# OOBD-Cup_v6.net
KiCad netlist of a schematic drawn in EAGLE
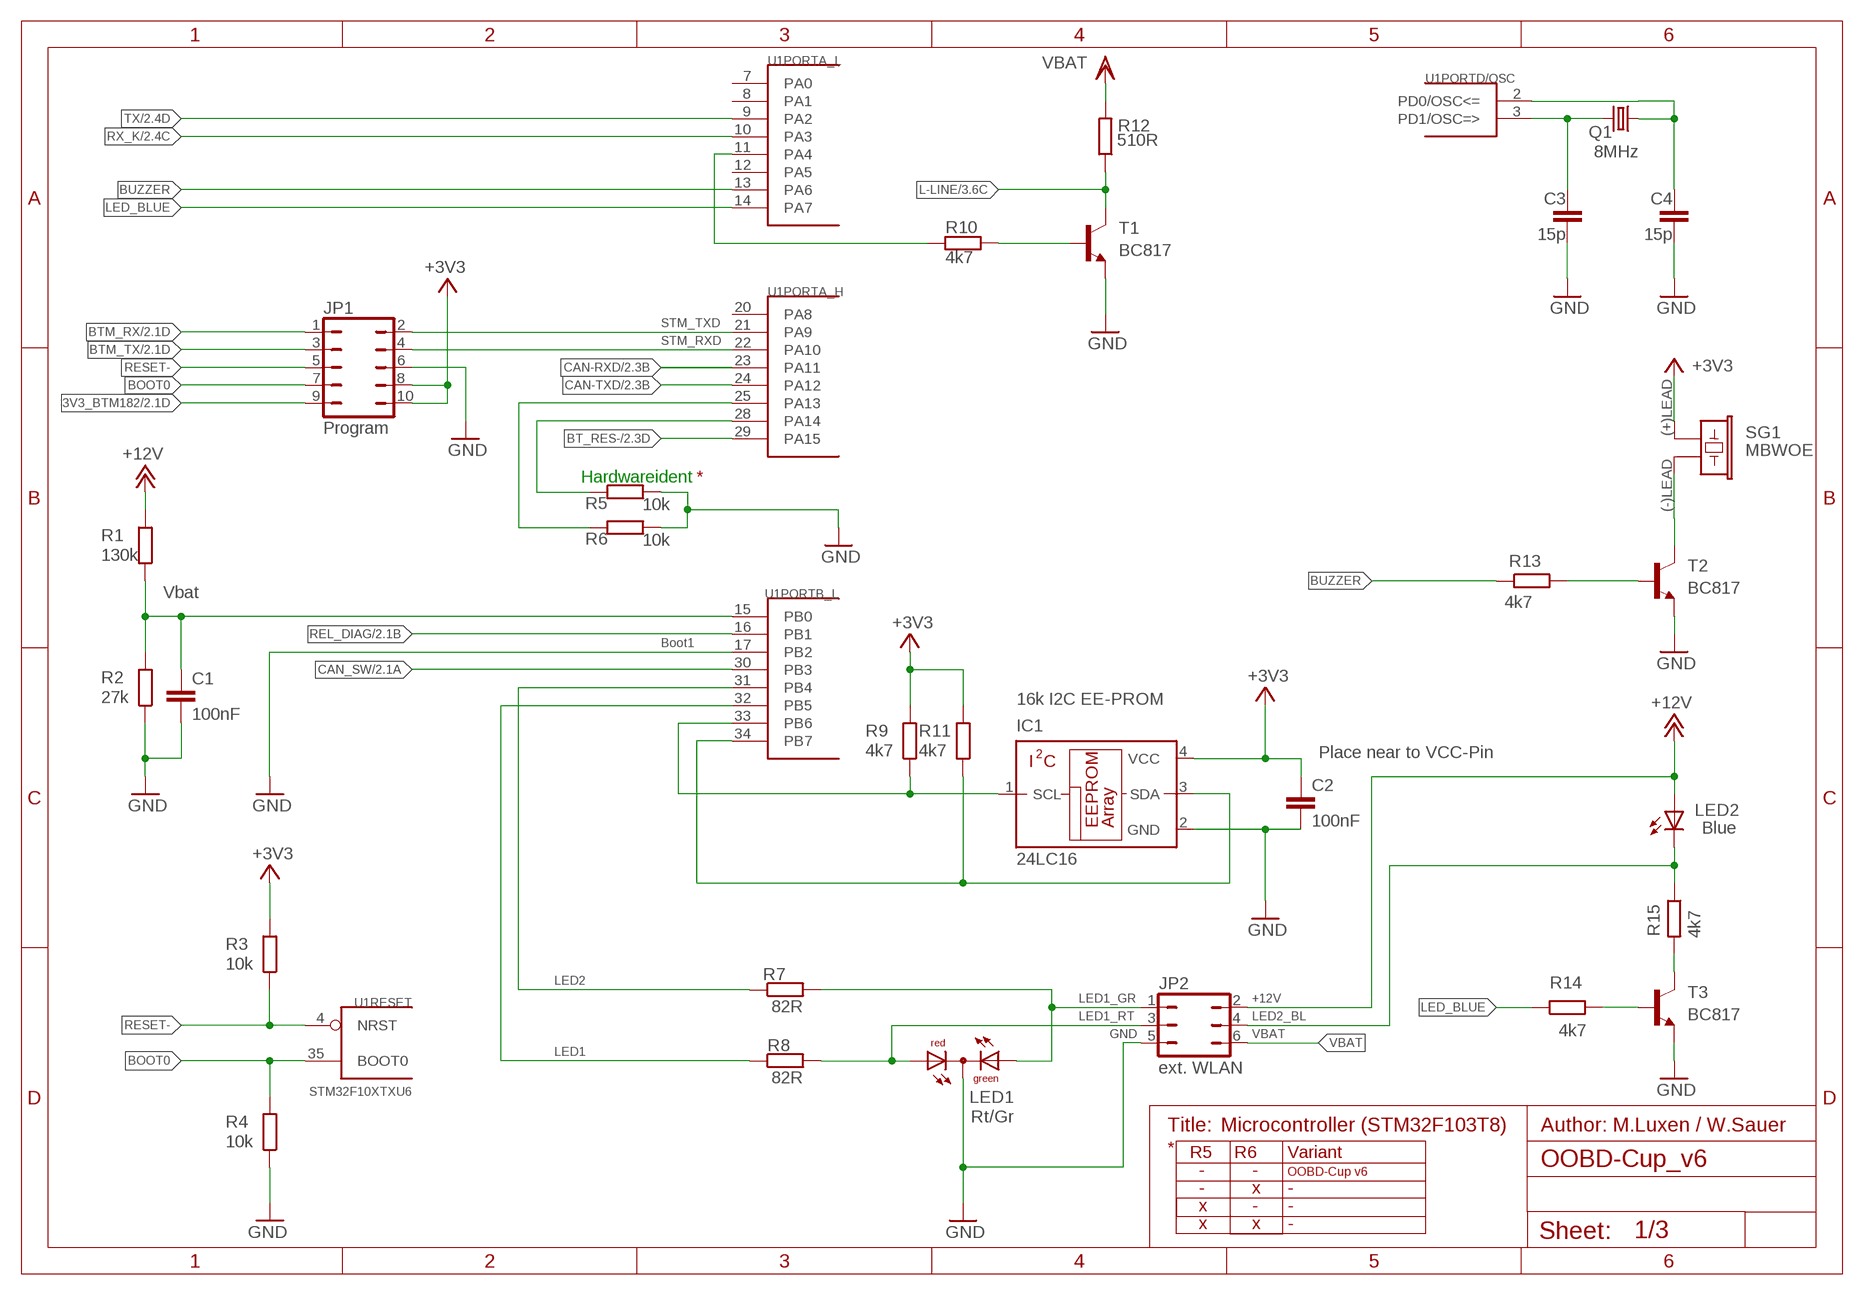
[diagram p0: schematic, sheet 1]
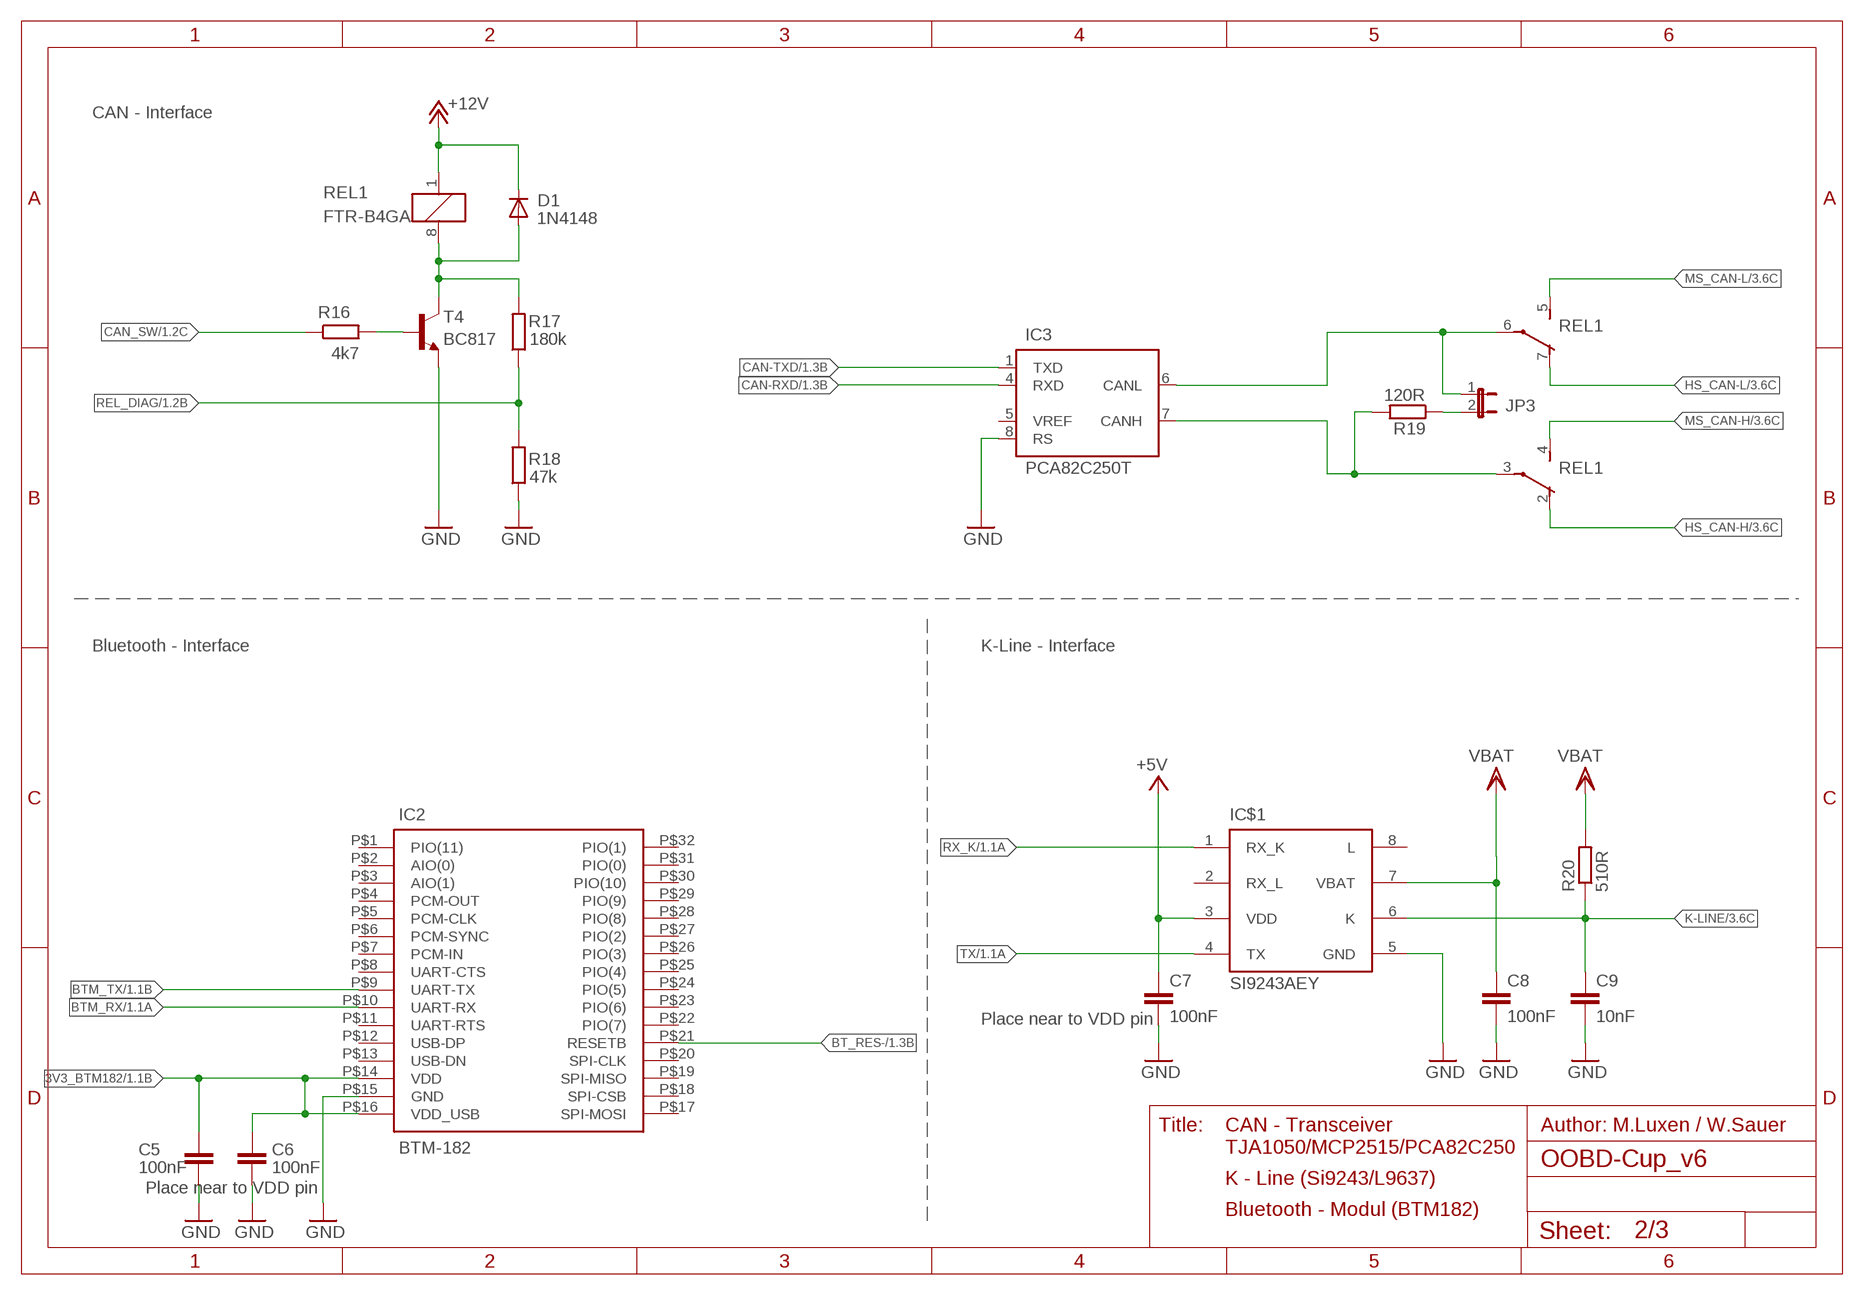
[diagram p1: schematic, sheet 2]
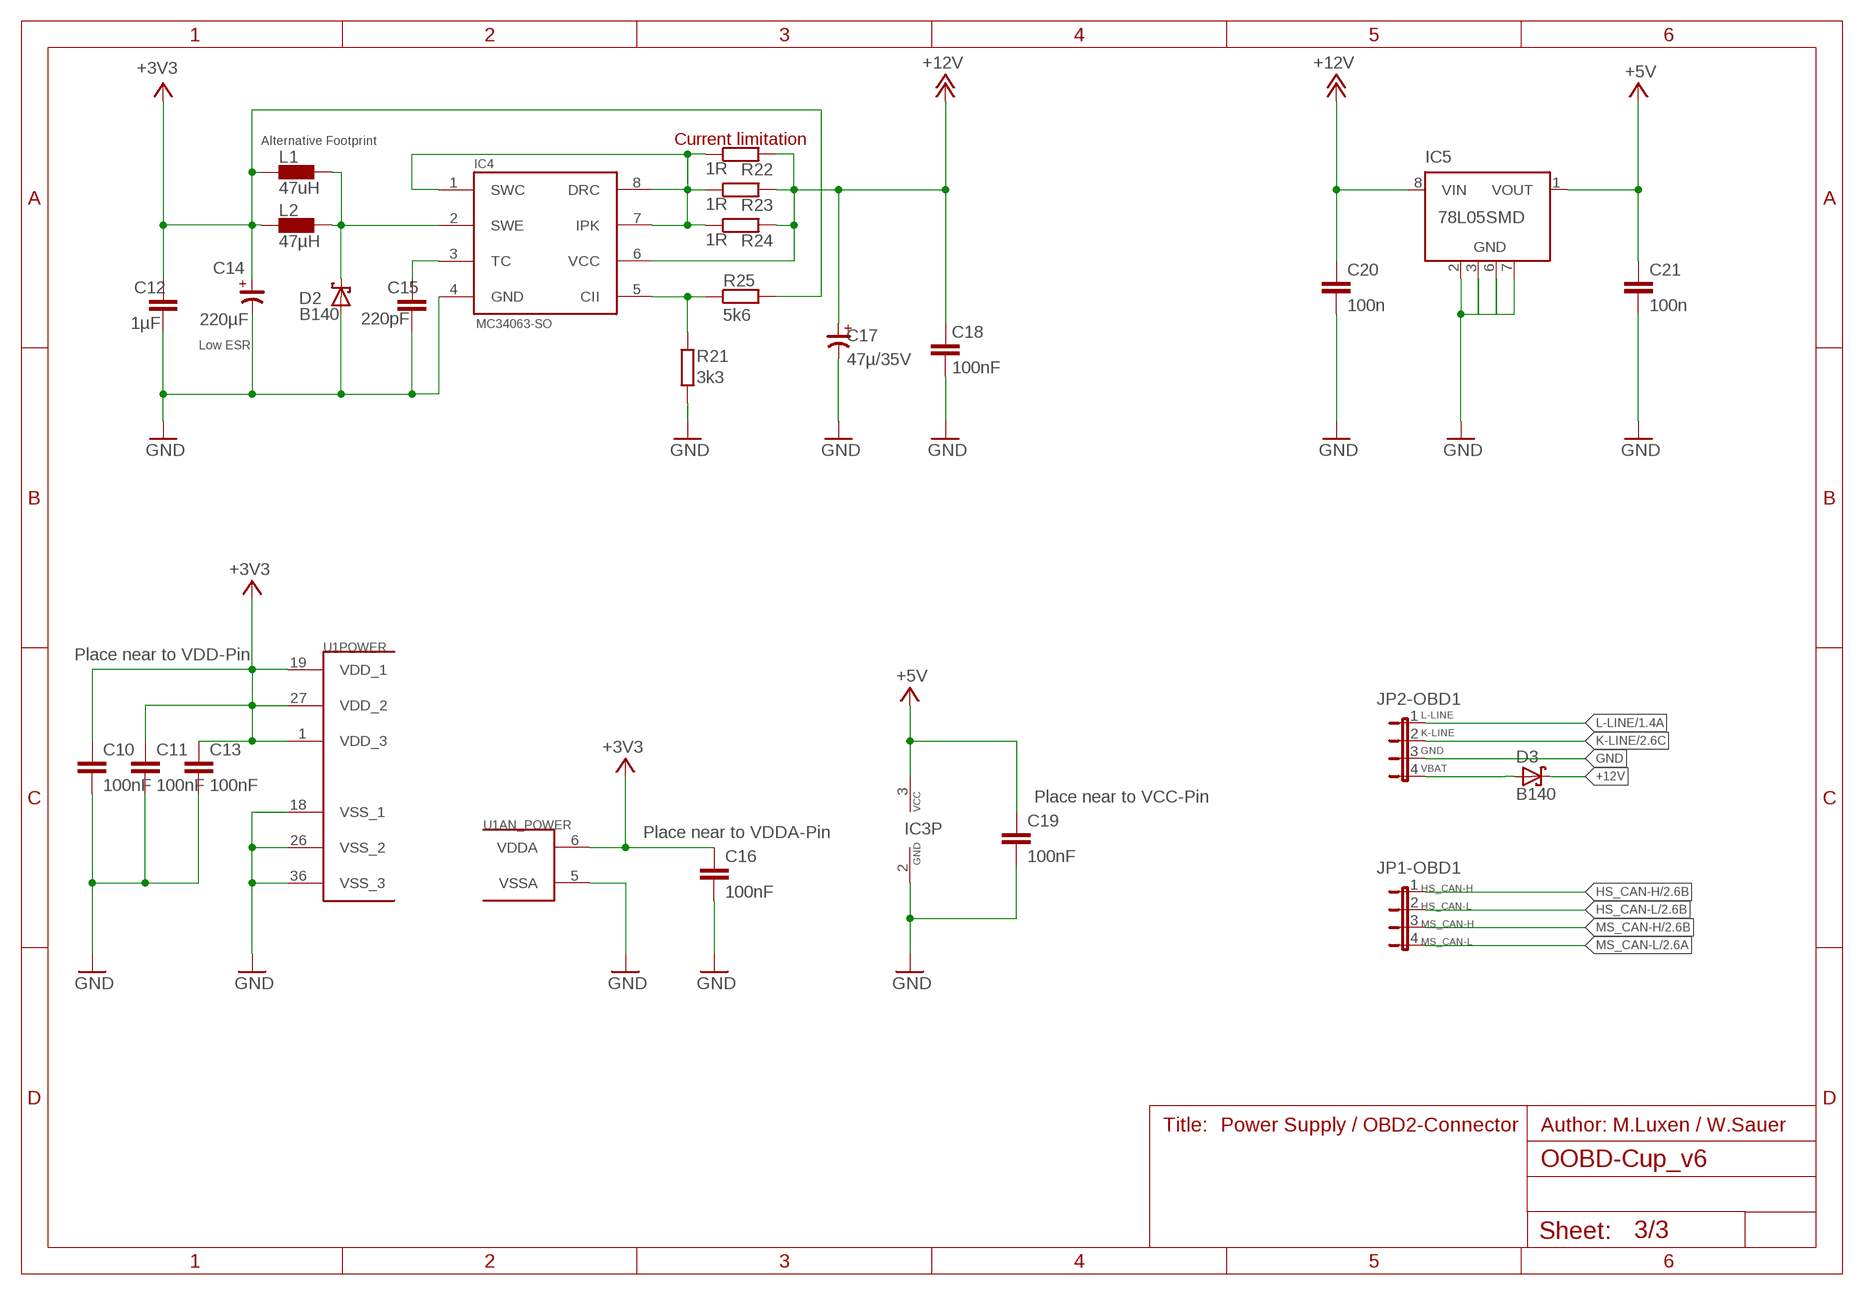
[diagram p2: schematic, sheet 3]

(export (version "E")
  (design (tool "Eeschema 10.0.6"))
  (components
    (comp (ref "C5")
      (value "100nF")
      (footprint "eagle-import:C0603")
      (libsource (lib "eagle-import") (part "C-EUC0603"))
    )
    (comp (ref "C6")
      (value "100nF")
      (footprint "eagle-import:C0603")
      (libsource (lib "eagle-import") (part "C-EUC0603"))
    )
    (comp (ref "C7")
      (value "100nF")
      (footprint "eagle-import:C0603")
      (libsource (lib "eagle-import") (part "resistor_C-EUC0603"))
    )
    (comp (ref "C8")
      (value "100nF")
      (footprint "eagle-import:C0603")
      (libsource (lib "eagle-import") (part "resistor_C-EUC0603"))
    )
    (comp (ref "C9")
      (value "10nF")
      (footprint "eagle-import:C0603")
      (libsource (lib "eagle-import") (part "resistor_C-EUC0603"))
    )
    (comp (ref "D1")
      (value "1N4148")
      (footprint "eagle-import:MINIMELF")
      (libsource (lib "eagle-import") (part "DIODE-MINIMELF"))
    )
    (comp (ref "IC$1")
      (value "SI9243AEY")
      (footprint "eagle-import:SO08")
      (libsource (lib "eagle-import") (part "SI9243AEY"))
    )
    (comp (ref "IC2")
      (value "BTM-182")
      (footprint "eagle-import:BTM-182")
      (libsource (lib "eagle-import") (part "BTM-182"))
    )
    (comp (ref "IC3")
      (value "PCA82C250T")
      (footprint "eagle-import:SO08")
      (libsource (lib "eagle-import") (part "PCA82C250T"))
    )
    (comp (ref "JP3")
      (value "JP1E")
      (footprint "eagle-import:JP1")
      (libsource (lib "eagle-import") (part "JP1E"))
    )
    (comp (ref "R16")
      (value "4k7")
      (footprint "eagle-import:R0603")
      (libsource (lib "eagle-import") (part "R-EU_R0603"))
    )
    (comp (ref "R17")
      (value "180k")
      (footprint "eagle-import:R0603")
      (libsource (lib "eagle-import") (part "R-EU_R0603"))
    )
    (comp (ref "R18")
      (value "47k")
      (footprint "eagle-import:R0603")
      (libsource (lib "eagle-import") (part "R-EU_R0603"))
    )
    (comp (ref "R19")
      (value "120R")
      (footprint "eagle-import:R0603")
      (libsource (lib "eagle-import") (part "resistor_R-EU_R0603"))
    )
    (comp (ref "R20")
      (value "510R")
      (footprint "eagle-import:R0603")
      (libsource (lib "eagle-import") (part "resistor_R-EU_R0603"))
    )
    (comp (ref "REL1")
      (value "FTR-B4GA")
      (footprint "eagle-import:FTR-B4GA")
      (fields (field (name "MPN") "FTR-B4GAxxxZ"))
      (libsource (lib "eagle-import") (part "FTR-B4GA"))
    )
    (comp (ref "T4")
      (value "BC817")
      (footprint "eagle-import:SOT23")
      (libsource (lib "eagle-import") (part "BC847"))
    )
    (comp (ref "C1")
      (value "100nF")
      (footprint "eagle-import:C0603")
      (libsource (lib "eagle-import") (part "resistor_C-EUC0603"))
    )
    (comp (ref "C2")
      (value "100nF")
      (footprint "eagle-import:C0603")
      (libsource (lib "eagle-import") (part "C-EUC0603"))
    )
    (comp (ref "C3")
      (value "15p")
      (footprint "eagle-import:C0603")
      (libsource (lib "eagle-import") (part "resistor_C-EUC0603"))
    )
    (comp (ref "C4")
      (value "15p")
      (footprint "eagle-import:C0603")
      (libsource (lib "eagle-import") (part "resistor_C-EUC0603"))
    )
    (comp (ref "IC1")
      (value "24LC16")
      (footprint "eagle-import:SOT23-5L")
      (fields (field (name "MF") "MICROCHIP") (field (name "MPN") "24LC00T-I/OT"))
      (libsource (lib "eagle-import") (part "2400OTLC"))
    )
    (comp (ref "JP1")
      (value "Program")
      (footprint "eagle-import:JP5Q")
      (libsource (lib "eagle-import") (part "JP5Q"))
    )
    (comp (ref "JP2")
      (value "ext. WLAN")
      (footprint "eagle-import:JP3Q")
      (libsource (lib "eagle-import") (part "JP3Q"))
    )
    (comp (ref "LED1")
      (value "Rt/Gr")
      (footprint "eagle-import:DUOLED2X5")
      (libsource (lib "eagle-import") (part "DUOLED2X5"))
    )
    (comp (ref "LED2")
      (value "Blue")
      (footprint "eagle-import:U57X32")
      (libsource (lib "eagle-import") (part "LEDSQR5.7X3.2"))
    )
    (comp (ref "Q1")
      (value "8MHz")
      (footprint "eagle-import:CTS406")
      (libsource (lib "eagle-import") (part "CRYSTALCTS406"))
    )
    (comp (ref "R1")
      (value "130k")
      (footprint "eagle-import:R0603")
      (libsource (lib "eagle-import") (part "resistor_R-EU_R0603"))
    )
    (comp (ref "R2")
      (value "27k")
      (footprint "eagle-import:R0603")
      (libsource (lib "eagle-import") (part "resistor_R-EU_R0603"))
    )
    (comp (ref "R3")
      (value "10k")
      (footprint "eagle-import:R0603")
      (libsource (lib "eagle-import") (part "resistor_R-EU_R0603"))
    )
    (comp (ref "R4")
      (value "10k")
      (footprint "eagle-import:R0603")
      (libsource (lib "eagle-import") (part "resistor_R-EU_R0603"))
    )
    (comp (ref "R5")
      (value "10k")
      (footprint "eagle-import:R0603")
      (libsource (lib "eagle-import") (part "R-EU_R0603"))
    )
    (comp (ref "R6")
      (value "10k")
      (footprint "eagle-import:R0603")
      (libsource (lib "eagle-import") (part "R-EU_R0603"))
    )
    (comp (ref "R7")
      (value "82R")
      (footprint "eagle-import:R0603")
      (libsource (lib "eagle-import") (part "R-EU_R0603"))
    )
    (comp (ref "R8")
      (value "82R")
      (footprint "eagle-import:R0603")
      (libsource (lib "eagle-import") (part "R-EU_R0603"))
    )
    (comp (ref "R9")
      (value "4k7")
      (footprint "eagle-import:R0603")
      (libsource (lib "eagle-import") (part "resistor_R-EU_R0603"))
    )
    (comp (ref "R10")
      (value "4k7")
      (footprint "eagle-import:R0603")
      (libsource (lib "eagle-import") (part "R-EU_R0603"))
    )
    (comp (ref "R11")
      (value "4k7")
      (footprint "eagle-import:R0603")
      (libsource (lib "eagle-import") (part "resistor_R-EU_R0603"))
    )
    (comp (ref "R12")
      (value "510R")
      (footprint "eagle-import:R0603")
      (libsource (lib "eagle-import") (part "R-EU_R0603"))
    )
    (comp (ref "R13")
      (value "4k7")
      (footprint "eagle-import:R0603")
      (libsource (lib "eagle-import") (part "R-EU_R0603"))
    )
    (comp (ref "R14")
      (value "4k7")
      (footprint "eagle-import:R0603")
      (libsource (lib "eagle-import") (part "R-EU_R0603"))
    )
    (comp (ref "R15")
      (value "4k7")
      (footprint "eagle-import:R0603")
      (libsource (lib "eagle-import") (part "R-EU_R0603"))
    )
    (comp (ref "SG1")
      (value "MBWOE")
      (footprint "eagle-import:BME0603SA")
      (fields (field (name "MF") "Grewus"))
      (libsource (lib "eagle-import") (part "MBWOE"))
    )
    (comp (ref "T1")
      (value "BC817")
      (footprint "eagle-import:SOT23")
      (libsource (lib "eagle-import") (part "BC847"))
    )
    (comp (ref "T2")
      (value "BC817")
      (footprint "eagle-import:SOT23")
      (libsource (lib "eagle-import") (part "BC847"))
    )
    (comp (ref "T3")
      (value "BC817")
      (footprint "eagle-import:SOT23")
      (libsource (lib "eagle-import") (part "BC847"))
    )
    (comp (ref "U1")
      (value "STM32F10XTXU6")
      (footprint "eagle-import:VFQFPN36")
      (libsource (lib "eagle-import") (part "STM32F10XTXU6"))
    )
    (comp (ref "C10")
      (value "100nF")
      (footprint "eagle-import:C0603")
      (libsource (lib "eagle-import") (part "resistor_C-EUC0603"))
    )
    (comp (ref "C11")
      (value "100nF")
      (footprint "eagle-import:C0603")
      (libsource (lib "eagle-import") (part "resistor_C-EUC0603"))
    )
    (comp (ref "C12")
      (value "1µF")
      (footprint "eagle-import:C0603K")
      (libsource (lib "eagle-import") (part "C-EUC0603K"))
    )
    (comp (ref "C13")
      (value "100nF")
      (footprint "eagle-import:C0603")
      (libsource (lib "eagle-import") (part "resistor_C-EUC0603"))
    )
    (comp (ref "C14")
      (value "220µF")
      (footprint "eagle-import:C6032-TE-C")
      (libsource (lib "eagle-import") (part "CP_6032-TE-C"))
    )
    (comp (ref "C15")
      (value "220pF")
      (footprint "eagle-import:C0603K")
      (libsource (lib "eagle-import") (part "C-EUC0603K"))
    )
    (comp (ref "C16")
      (value "100nF")
      (footprint "eagle-import:C0603")
      (libsource (lib "eagle-import") (part "resistor_C-EUC0603"))
    )
    (comp (ref "C17")
      (value "47µ/35V")
      (footprint "eagle-import:SV-D")
      (libsource (lib "eagle-import") (part "CP-SV-D"))
    )
    (comp (ref "C18")
      (value "100nF")
      (footprint "eagle-import:C0603K")
      (libsource (lib "eagle-import") (part "C-EUC0603K"))
    )
    (comp (ref "C19")
      (value "100nF")
      (footprint "eagle-import:C0603")
      (libsource (lib "eagle-import") (part "resistor_C-EUC0603"))
    )
    (comp (ref "C20")
      (value "100n")
      (footprint "eagle-import:C0603")
      (libsource (lib "eagle-import") (part "resistor_C-EUC0603"))
    )
    (comp (ref "C21")
      (value "100n")
      (footprint "eagle-import:C0603")
      (libsource (lib "eagle-import") (part "resistor_C-EUC0603"))
    )
    (comp (ref "D2")
      (value "B140")
      (footprint "eagle-import:SMB")
      (libsource (lib "eagle-import") (part "SCHOTTKY-DIODESMD"))
    )
    (comp (ref "D3")
      (value "B140")
      (footprint "eagle-import:SMB")
      (libsource (lib "eagle-import") (part "SCHOTTKY-DIODESMD"))
    )
    (comp (ref "IC4")
      (value "MC34063-SO")
      (footprint "eagle-import:SO8")
      (libsource (lib "eagle-import") (part "MC34063-SO"))
    )
    (comp (ref "IC5")
      (value "78L05SMD")
      (footprint "eagle-import:SO08")
      (libsource (lib "eagle-import") (part "78LSMD05"))
    )
    (comp (ref "JP1-OBD1")
      (value "JP4E")
      (footprint "eagle-import:JP4")
      (libsource (lib "eagle-import") (part "JP4E"))
    )
    (comp (ref "JP2-OBD1")
      (value "JP4E")
      (footprint "eagle-import:JP4")
      (libsource (lib "eagle-import") (part "JP4E"))
    )
    (comp (ref "L1")
      (value "47uH")
      (footprint "eagle-import:PIS2408")
      (libsource (lib "eagle-import") (part "PIS2408"))
    )
    (comp (ref "L2")
      (value "47µH")
      (footprint "eagle-import:07HCP-XXXX-50")
      (libsource (lib "eagle-import") (part "07HCP-XXXX-50"))
    )
    (comp (ref "R21")
      (value "3k3")
      (footprint "eagle-import:R0603")
      (libsource (lib "eagle-import") (part "R-EU_R0603"))
    )
    (comp (ref "R22")
      (value "1R")
      (footprint "eagle-import:R0805")
      (libsource (lib "eagle-import") (part "R-EU_R0805"))
    )
    (comp (ref "R23")
      (value "1R")
      (footprint "eagle-import:R0805")
      (libsource (lib "eagle-import") (part "R-EU_R0805"))
    )
    (comp (ref "R24")
      (value "1R")
      (footprint "eagle-import:R0805")
      (libsource (lib "eagle-import") (part "R-EU_R0805"))
    )
    (comp (ref "R25")
      (value "5k6")
      (footprint "eagle-import:R0603")
      (libsource (lib "eagle-import") (part "R-EU_R0603"))
    )
  )
  (nets
    (net (code "1") (name "+3V3") (class "Default")
      (node (ref "C10") (pin "1") (pinfunction "1_1") (pintype "passive"))
      (node (ref "C11") (pin "1") (pinfunction "1_1") (pintype "passive"))
      (node (ref "C12") (pin "1") (pinfunction "1_1") (pintype "passive"))
      (node (ref "C13") (pin "1") (pinfunction "1_1") (pintype "passive"))
      (node (ref "C14") (pin "+") (pinfunction "+_+") (pintype "passive"))
      (node (ref "C16") (pin "1") (pinfunction "1_1") (pintype "passive"))
      (node (ref "C2") (pin "1") (pinfunction "1_1") (pintype "passive"))
      (node (ref "IC1") (pin "4") (pinfunction "VCC_4") (pintype "power_in"))
      (node (ref "JP1") (pin "10") (pinfunction "10_10") (pintype "passive"))
      (node (ref "JP1") (pin "8") (pinfunction "8_8") (pintype "passive"))
      (node (ref "L1") (pin "P$1") (pinfunction "P$1_P$1") (pintype "bidirectional"))
      (node (ref "L2") (pin "1") (pinfunction "P$1_1") (pintype "bidirectional"))
      (node (ref "R11") (pin "2") (pinfunction "2_2") (pintype "passive"))
      (node (ref "R25") (pin "2") (pinfunction "2_2") (pintype "passive"))
      (node (ref "R3") (pin "2") (pinfunction "2_2") (pintype "passive"))
      (node (ref "R9") (pin "2") (pinfunction "2_2") (pintype "passive"))
      (node (ref "SG1") (pin "(+)LEAD") (pinfunction "1_(+)LEAD") (pintype "passive"))
      (node (ref "U1") (pin "1") (pinfunction "VDD_3_1") (pintype "power_in"))
      (node (ref "U1") (pin "19") (pinfunction "VDD_1_19") (pintype "power_in"))
      (node (ref "U1") (pin "27") (pinfunction "VDD_2_27") (pintype "power_in"))
      (node (ref "U1") (pin "6") (pinfunction "VDDA_6") (pintype "power_in"))
    )
    (net (code "2") (name "+5V") (class "Default")
      (node (ref "C19") (pin "1") (pinfunction "1_1") (pintype "passive"))
      (node (ref "C21") (pin "1") (pinfunction "1_1") (pintype "passive"))
      (node (ref "C7") (pin "1") (pinfunction "1_1") (pintype "passive"))
      (node (ref "IC$1") (pin "3") (pinfunction "VDD_3") (pintype "bidirectional"))
      (node (ref "IC3") (pin "3") (pinfunction "VCC_3") (pintype "power_in"))
      (node (ref "IC5") (pin "1") (pinfunction "VOUT_1") (pintype "output"))
    )
    (net (code "3") (name "+12V") (class "Default")
      (node (ref "C17") (pin "+") (pinfunction "+_+") (pintype "passive"))
      (node (ref "C18") (pin "1") (pinfunction "1_1") (pintype "passive"))
      (node (ref "C20") (pin "1") (pinfunction "1_1") (pintype "passive"))
      (node (ref "D1") (pin "C") (pinfunction "C_C") (pintype "passive"))
      (node (ref "D3") (pin "C") (pinfunction "C_C") (pintype "passive"))
      (node (ref "IC4") (pin "6") (pinfunction "VCC_6") (pintype "bidirectional"))
      (node (ref "IC5") (pin "8") (pinfunction "VIN_8") (pintype "passive"))
      (node (ref "JP2") (pin "2") (pinfunction "2_2") (pintype "passive"))
      (node (ref "LED2") (pin "A") (pinfunction "A_A") (pintype "passive"))
      (node (ref "R1") (pin "2") (pinfunction "2_2") (pintype "passive"))
      (node (ref "R22") (pin "2") (pinfunction "2_2") (pintype "passive"))
      (node (ref "R23") (pin "2") (pinfunction "2_2") (pintype "passive"))
      (node (ref "R24") (pin "2") (pinfunction "2_2") (pintype "passive"))
      (node (ref "REL1") (pin "1") (pinfunction "1_1") (pintype "passive"))
    )
    (net (code "4") (name "3V3_BTM182") (class "Default")
      (node (ref "C5") (pin "1") (pinfunction "1_1") (pintype "passive"))
      (node (ref "C6") (pin "1") (pinfunction "1_1") (pintype "passive"))
      (node (ref "IC2") (pin "P$14") (pinfunction "VDD_P$14") (pintype "power_in"))
      (node (ref "IC2") (pin "P$16") (pinfunction "VDD_USB_P$16") (pintype "power_in"))
      (node (ref "JP1") (pin "9") (pinfunction "9_9") (pintype "passive"))
    )
    (net (code "5") (name "BOOT0") (class "Default")
      (node (ref "JP1") (pin "7") (pinfunction "7_7") (pintype "passive"))
      (node (ref "R4") (pin "2") (pinfunction "2_2") (pintype "passive"))
      (node (ref "U1") (pin "35") (pinfunction "BOOT0_35") (pintype "input"))
    )
    (net (code "6") (name "BTM_RX") (class "Default")
      (node (ref "IC2") (pin "P$10") (pinfunction "UART-RX_P$10") (pintype "input"))
      (node (ref "JP1") (pin "1") (pinfunction "1_1") (pintype "passive"))
    )
    (net (code "7") (name "BTM_TX") (class "Default")
      (node (ref "IC2") (pin "P$9") (pinfunction "UART-TX_P$9") (pintype "output"))
      (node (ref "JP1") (pin "3") (pinfunction "3_3") (pintype "passive"))
    )
    (net (code "8") (name "BT_RES-") (class "Default")
      (node (ref "IC2") (pin "P$21") (pinfunction "RESETB_P$21") (pintype "input"))
      (node (ref "U1") (pin "29") (pinfunction "PA15_29") (pintype "bidirectional"))
    )
    (net (code "9") (name "BUZZER") (class "Default")
      (node (ref "R13") (pin "1") (pinfunction "1_1") (pintype "passive"))
      (node (ref "U1") (pin "13") (pinfunction "PA6_13") (pintype "bidirectional"))
    )
    (net (code "10") (name "CAN-RXD") (class "Default")
      (node (ref "IC3") (pin "4") (pinfunction "RXD_4") (pintype "bidirectional"))
      (node (ref "U1") (pin "23") (pinfunction "PA11_23") (pintype "bidirectional"))
    )
    (net (code "11") (name "CAN-TXD") (class "Default")
      (node (ref "IC3") (pin "1") (pinfunction "TXD_1") (pintype "bidirectional"))
      (node (ref "U1") (pin "24") (pinfunction "PA12_24") (pintype "bidirectional"))
    )
    (net (code "12") (name "CAN_SW") (class "Default")
      (node (ref "R16") (pin "1") (pinfunction "1_1") (pintype "passive"))
      (node (ref "U1") (pin "30") (pinfunction "PB3_30") (pintype "bidirectional"))
    )
    (net (code "13") (name "GND") (class "Default")
      (node (ref "C1") (pin "2") (pinfunction "2_2") (pintype "passive"))
      (node (ref "C10") (pin "2") (pinfunction "2_2") (pintype "passive"))
      (node (ref "C11") (pin "2") (pinfunction "2_2") (pintype "passive"))
      (node (ref "C12") (pin "2") (pinfunction "2_2") (pintype "passive"))
      (node (ref "C13") (pin "2") (pinfunction "2_2") (pintype "passive"))
      (node (ref "C14") (pin "-") (pinfunction "-_-") (pintype "passive"))
      (node (ref "C15") (pin "2") (pinfunction "2_2") (pintype "passive"))
      (node (ref "C16") (pin "2") (pinfunction "2_2") (pintype "passive"))
      (node (ref "C17") (pin "-") (pinfunction "-_-") (pintype "passive"))
      (node (ref "C18") (pin "2") (pinfunction "2_2") (pintype "passive"))
      (node (ref "C19") (pin "2") (pinfunction "2_2") (pintype "passive"))
      (node (ref "C2") (pin "2") (pinfunction "2_2") (pintype "passive"))
      (node (ref "C20") (pin "2") (pinfunction "2_2") (pintype "passive"))
      (node (ref "C21") (pin "2") (pinfunction "2_2") (pintype "passive"))
      (node (ref "C3") (pin "1") (pinfunction "1_1") (pintype "passive"))
      (node (ref "C4") (pin "1") (pinfunction "1_1") (pintype "passive"))
      (node (ref "C5") (pin "2") (pinfunction "2_2") (pintype "passive"))
      (node (ref "C6") (pin "2") (pinfunction "2_2") (pintype "passive"))
      (node (ref "C7") (pin "2") (pinfunction "2_2") (pintype "passive"))
      (node (ref "C8") (pin "2") (pinfunction "2_2") (pintype "passive"))
      (node (ref "C9") (pin "2") (pinfunction "2_2") (pintype "passive"))
      (node (ref "D2") (pin "A") (pinfunction "A_A") (pintype "passive"))
      (node (ref "IC$1") (pin "5") (pinfunction "GND_5") (pintype "bidirectional"))
      (node (ref "IC1") (pin "2") (pinfunction "GND_2") (pintype "power_in"))
      (node (ref "IC2") (pin "P$15") (pinfunction "GND_P$15") (pintype "power_in"))
      (node (ref "IC3") (pin "2") (pinfunction "GND_2") (pintype "power_in"))
      (node (ref "IC3") (pin "8") (pinfunction "RS_8") (pintype "bidirectional"))
      (node (ref "IC4") (pin "4") (pinfunction "GND_4") (pintype "power_in"))
      (node (ref "IC5") (pin "2") (pinfunction "GND_2") (pintype "power_in"))
      (node (ref "IC5") (pin "3") (pinfunction "GND_3") (pintype "power_in"))
      (node (ref "IC5") (pin "6") (pinfunction "GND_6") (pintype "power_in"))
      (node (ref "IC5") (pin "7") (pinfunction "GND_7") (pintype "power_in"))
      (node (ref "JP1") (pin "6") (pinfunction "6_6") (pintype "passive"))
      (node (ref "JP2") (pin "5") (pinfunction "5_5") (pintype "passive"))
      (node (ref "JP2-OBD1") (pin "3") (pinfunction "3_3") (pintype "passive"))
      (node (ref "LED1") (pin "K") (pinfunction "C_K") (pintype "passive"))
      (node (ref "R18") (pin "1") (pinfunction "1_1") (pintype "passive"))
      (node (ref "R2") (pin "1") (pinfunction "1_1") (pintype "passive"))
      (node (ref "R21") (pin "2") (pinfunction "2_2") (pintype "passive"))
      (node (ref "R4") (pin "1") (pinfunction "1_1") (pintype "passive"))
      (node (ref "R5") (pin "2") (pinfunction "2_2") (pintype "passive"))
      (node (ref "R6") (pin "2") (pinfunction "2_2") (pintype "passive"))
      (node (ref "T1") (pin "2") (pinfunction "E_2") (pintype "passive"))
      (node (ref "T2") (pin "2") (pinfunction "E_2") (pintype "passive"))
      (node (ref "T3") (pin "2") (pinfunction "E_2") (pintype "passive"))
      (node (ref "T4") (pin "2") (pinfunction "E_2") (pintype "passive"))
      (node (ref "U1") (pin "17") (pinfunction "PB2_17") (pintype "bidirectional"))
      (node (ref "U1") (pin "18") (pinfunction "VSS_1_18") (pintype "power_in"))
      (node (ref "U1") (pin "26") (pinfunction "VSS_2_26") (pintype "power_in"))
      (node (ref "U1") (pin "36") (pinfunction "VSS_3_36") (pintype "power_in"))
      (node (ref "U1") (pin "5") (pinfunction "VSSA_5") (pintype "power_in"))
    )
    (net (code "14") (name "HS_CAN-H") (class "Default")
      (node (ref "JP1-OBD1") (pin "1") (pinfunction "1_1") (pintype "passive"))
      (node (ref "REL1") (pin "2") (pinfunction "O_2") (pintype "passive"))
    )
    (net (code "15") (name "HS_CAN-L") (class "Default")
      (node (ref "JP1-OBD1") (pin "2") (pinfunction "2_2") (pintype "passive"))
      (node (ref "REL1") (pin "7") (pinfunction "O_7") (pintype "passive"))
    )
    (net (code "16") (name "K-LINE") (class "Default")
      (node (ref "C9") (pin "1") (pinfunction "1_1") (pintype "passive"))
      (node (ref "IC$1") (pin "6") (pinfunction "K_6") (pintype "bidirectional"))
      (node (ref "JP2-OBD1") (pin "2") (pinfunction "2_2") (pintype "passive"))
      (node (ref "R20") (pin "1") (pinfunction "1_1") (pintype "passive"))
    )
    (net (code "17") (name "L-LINE") (class "Default")
      (node (ref "JP2-OBD1") (pin "1") (pinfunction "1_1") (pintype "passive"))
      (node (ref "R12") (pin "1") (pinfunction "1_1") (pintype "passive"))
      (node (ref "T1") (pin "3") (pinfunction "C_3") (pintype "passive"))
    )
    (net (code "18") (name "LED1") (class "Default")
      (node (ref "R8") (pin "1") (pinfunction "1_1") (pintype "passive"))
      (node (ref "U1") (pin "32") (pinfunction "PB5_32") (pintype "bidirectional"))
    )
    (net (code "19") (name "LED1_GR") (class "Default")
      (node (ref "JP2") (pin "1") (pinfunction "1_1") (pintype "passive"))
      (node (ref "LED1") (pin "AG") (pinfunction "AG_AG") (pintype "passive"))
      (node (ref "R7") (pin "2") (pinfunction "2_2") (pintype "passive"))
    )
    (net (code "20") (name "LED1_RT") (class "Default")
      (node (ref "JP2") (pin "3") (pinfunction "3_3") (pintype "passive"))
      (node (ref "LED1") (pin "AR") (pinfunction "AR_AR") (pintype "passive"))
      (node (ref "R8") (pin "2") (pinfunction "2_2") (pintype "passive"))
    )
    (net (code "21") (name "LED2") (class "Default")
      (node (ref "R7") (pin "1") (pinfunction "1_1") (pintype "passive"))
      (node (ref "U1") (pin "31") (pinfunction "PB4_31") (pintype "bidirectional"))
    )
    (net (code "22") (name "LED2_BL") (class "Default")
      (node (ref "JP2") (pin "4") (pinfunction "4_4") (pintype "passive"))
      (node (ref "LED2") (pin "K") (pinfunction "C_K") (pintype "passive"))
      (node (ref "R15") (pin "1") (pinfunction "1_1") (pintype "passive"))
    )
    (net (code "23") (name "LED_BLUE") (class "Default")
      (node (ref "R14") (pin "1") (pinfunction "1_1") (pintype "passive"))
      (node (ref "U1") (pin "14") (pinfunction "PA7_14") (pintype "bidirectional"))
    )
    (net (code "24") (name "MS_CAN-H") (class "Default")
      (node (ref "JP1-OBD1") (pin "3") (pinfunction "3_3") (pintype "passive"))
      (node (ref "REL1") (pin "4") (pinfunction "S_4") (pintype "passive"))
    )
    (net (code "25") (name "MS_CAN-L") (class "Default")
      (node (ref "JP1-OBD1") (pin "4") (pinfunction "4_4") (pintype "passive"))
      (node (ref "REL1") (pin "5") (pinfunction "S_5") (pintype "passive"))
    )
    (net (code "26") (name "Net-(IC1-SCL)") (class "Default")
      (node (ref "IC1") (pin "1") (pinfunction "SCL_1") (pintype "input"))
      (node (ref "R9") (pin "1") (pinfunction "1_1") (pintype "passive"))
      (node (ref "U1") (pin "33") (pinfunction "PB6_33") (pintype "bidirectional"))
    )
    (net (code "27") (name "Net-(IC1-SDA)") (class "Default")
      (node (ref "IC1") (pin "3") (pinfunction "SDA_3") (pintype "bidirectional"))
      (node (ref "R11") (pin "1") (pinfunction "1_1") (pintype "passive"))
      (node (ref "U1") (pin "34") (pinfunction "PB7_34") (pintype "bidirectional"))
    )
    (net (code "28") (name "Net-(IC3A-CANH)") (class "Default")
      (node (ref "IC3") (pin "7") (pinfunction "CANH_7") (pintype "bidirectional"))
      (node (ref "R19") (pin "2") (pinfunction "2_2") (pintype "passive"))
      (node (ref "REL1") (pin "3") (pinfunction "P_3") (pintype "passive"))
    )
    (net (code "29") (name "Net-(IC3A-CANL)") (class "Default")
      (node (ref "IC3") (pin "6") (pinfunction "CANL_6") (pintype "bidirectional"))
      (node (ref "JP3") (pin "1") (pinfunction "1_1") (pintype "passive"))
      (node (ref "REL1") (pin "6") (pinfunction "P_6") (pintype "passive"))
    )
    (net (code "30") (name "Net-(IC4-CII)") (class "Default")
      (node (ref "IC4") (pin "5") (pinfunction "CII_5") (pintype "bidirectional"))
      (node (ref "R21") (pin "1") (pinfunction "1_1") (pintype "passive"))
      (node (ref "R25") (pin "1") (pinfunction "1_1") (pintype "passive"))
    )
    (net (code "31") (name "Net-(IC4-DRC)") (class "Default")
      (node (ref "IC4") (pin "1") (pinfunction "SWC_1") (pintype "bidirectional"))
      (node (ref "IC4") (pin "7") (pinfunction "IPK_7") (pintype "bidirectional"))
      (node (ref "IC4") (pin "8") (pinfunction "DRC_8") (pintype "bidirectional"))
      (node (ref "R22") (pin "1") (pinfunction "1_1") (pintype "passive"))
      (node (ref "R23") (pin "1") (pinfunction "1_1") (pintype "passive"))
      (node (ref "R24") (pin "1") (pinfunction "1_1") (pintype "passive"))
    )
    (net (code "32") (name "Net-(IC4-SWE)") (class "Default")
      (node (ref "D2") (pin "C") (pinfunction "C_C") (pintype "passive"))
      (node (ref "IC4") (pin "2") (pinfunction "SWE_2") (pintype "bidirectional"))
      (node (ref "L1") (pin "P$2") (pinfunction "P$2_P$2") (pintype "bidirectional"))
      (node (ref "L2") (pin "2") (pinfunction "P$2_2") (pintype "bidirectional"))
    )
    (net (code "33") (name "Net-(IC4-TC)") (class "Default")
      (node (ref "C15") (pin "1") (pinfunction "1_1") (pintype "passive"))
      (node (ref "IC4") (pin "3") (pinfunction "TC_3") (pintype "bidirectional"))
    )
    (net (code "34") (name "Net-(JP3-Pad2)") (class "Default")
      (node (ref "JP3") (pin "2") (pinfunction "2_2") (pintype "passive"))
      (node (ref "R19") (pin "1") (pinfunction "1_1") (pintype "passive"))
    )
    (net (code "35") (name "Net-(Q1-2)") (class "Default")
      (node (ref "C3") (pin "2") (pinfunction "2_2") (pintype "passive"))
      (node (ref "Q1") (pin "3") (pinfunction "2_3") (pintype "passive"))
      (node (ref "U1") (pin "3") (pinfunction "PD1/OSC=>_3") (pintype "bidirectional"))
    )
    (net (code "36") (name "Net-(REL1A-2)") (class "Default")
      (node (ref "D1") (pin "A") (pinfunction "A_A") (pintype "passive"))
      (node (ref "R17") (pin "2") (pinfunction "2_2") (pintype "passive"))
      (node (ref "REL1") (pin "8") (pinfunction "2_8") (pintype "passive"))
      (node (ref "T4") (pin "3") (pinfunction "C_3") (pintype "passive"))
    )
    (net (code "37") (name "Net-(SG1-2)") (class "Default")
      (node (ref "SG1") (pin "(-)LEAD") (pinfunction "2_(-)LEAD") (pintype "passive"))
      (node (ref "T2") (pin "3") (pinfunction "C_3") (pintype "passive"))
    )
    (net (code "38") (name "Net-(T1-B)") (class "Default")
      (node (ref "R10") (pin "2") (pinfunction "2_2") (pintype "passive"))
      (node (ref "T1") (pin "1") (pinfunction "B_1") (pintype "passive"))
    )
    (net (code "39") (name "Net-(T2-B)") (class "Default")
      (node (ref "R13") (pin "2") (pinfunction "2_2") (pintype "passive"))
      (node (ref "T2") (pin "1") (pinfunction "B_1") (pintype "passive"))
    )
    (net (code "40") (name "Net-(T3-B)") (class "Default")
      (node (ref "R14") (pin "2") (pinfunction "2_2") (pintype "passive"))
      (node (ref "T3") (pin "1") (pinfunction "B_1") (pintype "passive"))
    )
    (net (code "41") (name "Net-(T3-C)") (class "Default")
      (node (ref "R15") (pin "2") (pinfunction "2_2") (pintype "passive"))
      (node (ref "T3") (pin "3") (pinfunction "C_3") (pintype "passive"))
    )
    (net (code "42") (name "Net-(T4-B)") (class "Default")
      (node (ref "R16") (pin "2") (pinfunction "2_2") (pintype "passive"))
      (node (ref "T4") (pin "1") (pinfunction "B_1") (pintype "passive"))
    )
    (net (code "43") (name "Net-(U1B-PA13)") (class "Default")
      (node (ref "R6") (pin "1") (pinfunction "1_1") (pintype "passive"))
      (node (ref "U1") (pin "25") (pinfunction "PA13_25") (pintype "bidirectional"))
    )
    (net (code "44") (name "Net-(U1B-PA14)") (class "Default")
      (node (ref "R5") (pin "1") (pinfunction "1_1") (pintype "passive"))
      (node (ref "U1") (pin "28") (pinfunction "PA14_28") (pintype "bidirectional"))
    )
    (net (code "45") (name "Net-(U1C-PA4)") (class "Default")
      (node (ref "R10") (pin "1") (pinfunction "1_1") (pintype "passive"))
      (node (ref "U1") (pin "11") (pinfunction "PA4_11") (pintype "bidirectional"))
    )
    (net (code "46") (name "Net-(U1D-PB0)") (class "Default")
      (node (ref "C1") (pin "1") (pinfunction "1_1") (pintype "passive"))
      (node (ref "R1") (pin "1") (pinfunction "1_1") (pintype "passive"))
      (node (ref "R2") (pin "2") (pinfunction "2_2") (pintype "passive"))
      (node (ref "U1") (pin "15") (pinfunction "PB0_15") (pintype "bidirectional"))
    )
    (net (code "47") (name "Net-(U1E-PD0{slash}OSC<=)") (class "Default")
      (node (ref "C4") (pin "2") (pinfunction "2_2") (pintype "passive"))
      (node (ref "Q1") (pin "1") (pinfunction "1_1") (pintype "passive"))
      (node (ref "U1") (pin "2") (pinfunction "PD0/OSC<=_2") (pintype "bidirectional"))
    )
    (net (code "48") (name "REL_DIAG") (class "Default")
      (node (ref "R17") (pin "1") (pinfunction "1_1") (pintype "passive"))
      (node (ref "R18") (pin "2") (pinfunction "2_2") (pintype "passive"))
      (node (ref "U1") (pin "16") (pinfunction "PB1_16") (pintype "bidirectional"))
    )
    (net (code "49") (name "RESET-") (class "Default")
      (node (ref "JP1") (pin "5") (pinfunction "5_5") (pintype "passive"))
      (node (ref "R3") (pin "1") (pinfunction "1_1") (pintype "passive"))
      (node (ref "U1") (pin "4") (pinfunction "NRST_4") (pintype "input"))
    )
    (net (code "50") (name "RX_K") (class "Default")
      (node (ref "IC$1") (pin "1") (pinfunction "RX_K_1") (pintype "bidirectional"))
      (node (ref "U1") (pin "10") (pinfunction "PA3_10") (pintype "bidirectional"))
    )
    (net (code "51") (name "STM_RXD") (class "Default")
      (node (ref "JP1") (pin "4") (pinfunction "4_4") (pintype "passive"))
      (node (ref "U1") (pin "22") (pinfunction "PA10_22") (pintype "bidirectional"))
    )
    (net (code "52") (name "STM_TXD") (class "Default")
      (node (ref "JP1") (pin "2") (pinfunction "2_2") (pintype "passive"))
      (node (ref "U1") (pin "21") (pinfunction "PA9_21") (pintype "bidirectional"))
    )
    (net (code "53") (name "TX") (class "Default")
      (node (ref "IC$1") (pin "4") (pinfunction "TX_4") (pintype "bidirectional"))
      (node (ref "U1") (pin "9") (pinfunction "PA2_9") (pintype "bidirectional"))
    )
    (net (code "54") (name "VBAT") (class "Default")
      (node (ref "C8") (pin "1") (pinfunction "1_1") (pintype "passive"))
      (node (ref "D3") (pin "A") (pinfunction "A_A") (pintype "passive"))
      (node (ref "IC$1") (pin "7") (pinfunction "VBAT_7") (pintype "bidirectional"))
      (node (ref "JP2") (pin "6") (pinfunction "6_6") (pintype "passive"))
      (node (ref "JP2-OBD1") (pin "4") (pinfunction "4_4") (pintype "passive"))
      (node (ref "R12") (pin "2") (pinfunction "2_2") (pintype "passive"))
      (node (ref "R20") (pin "2") (pinfunction "2_2") (pintype "passive"))
    )
    (net (code "55") (name "unconnected-(IC$1-L-Pad8)") (class "Default")
      (node (ref "IC$1") (pin "8") (pinfunction "L_8") (pintype "bidirectional"))
    )
    (net (code "56") (name "unconnected-(IC$1-RX_L-Pad2)") (class "Default")
      (node (ref "IC$1") (pin "2") (pinfunction "RX_L_2") (pintype "bidirectional"))
    )
    (net (code "57") (name "unconnected-(IC2-AIO(0)-PadP$2)") (class "Default")
      (node (ref "IC2") (pin "P$2") (pinfunction "AIO(0)_P$2") (pintype "bidirectional"))
    )
    (net (code "58") (name "unconnected-(IC2-AIO(1)-PadP$3)") (class "Default")
      (node (ref "IC2") (pin "P$3") (pinfunction "AIO(1)_P$3") (pintype "bidirectional"))
    )
    (net (code "59") (name "unconnected-(IC2-PCM-CLK-PadP$5)") (class "Default")
      (node (ref "IC2") (pin "P$5") (pinfunction "PCM-CLK_P$5") (pintype "bidirectional"))
    )
    (net (code "60") (name "unconnected-(IC2-PCM-IN-PadP$7)") (class "Default")
      (node (ref "IC2") (pin "P$7") (pinfunction "PCM-IN_P$7") (pintype "input"))
    )
    (net (code "61") (name "unconnected-(IC2-PCM-OUT-PadP$4)") (class "Default")
      (node (ref "IC2") (pin "P$4") (pinfunction "PCM-OUT_P$4") (pintype "output"))
    )
    (net (code "62") (name "unconnected-(IC2-PCM-SYNC-PadP$6)") (class "Default")
      (node (ref "IC2") (pin "P$6") (pinfunction "PCM-SYNC_P$6") (pintype "bidirectional"))
    )
    (net (code "63") (name "unconnected-(IC2-PIO(0)-PadP$31)") (class "Default")
      (node (ref "IC2") (pin "P$31") (pinfunction "PIO(0)_P$31") (pintype "bidirectional"))
    )
    (net (code "64") (name "unconnected-(IC2-PIO(1)-PadP$32)") (class "Default")
      (node (ref "IC2") (pin "P$32") (pinfunction "PIO(1)_P$32") (pintype "bidirectional"))
    )
    (net (code "65") (name "unconnected-(IC2-PIO(2)-PadP$27)") (class "Default")
      (node (ref "IC2") (pin "P$27") (pinfunction "PIO(2)_P$27") (pintype "bidirectional"))
    )
    (net (code "66") (name "unconnected-(IC2-PIO(3)-PadP$26)") (class "Default")
      (node (ref "IC2") (pin "P$26") (pinfunction "PIO(3)_P$26") (pintype "bidirectional"))
    )
    (net (code "67") (name "unconnected-(IC2-PIO(4)-PadP$25)") (class "Default")
      (node (ref "IC2") (pin "P$25") (pinfunction "PIO(4)_P$25") (pintype "bidirectional"))
    )
    (net (code "68") (name "unconnected-(IC2-PIO(5)-PadP$24)") (class "Default")
      (node (ref "IC2") (pin "P$24") (pinfunction "PIO(5)_P$24") (pintype "bidirectional"))
    )
    (net (code "69") (name "unconnected-(IC2-PIO(6)-PadP$23)") (class "Default")
      (node (ref "IC2") (pin "P$23") (pinfunction "PIO(6)_P$23") (pintype "bidirectional"))
    )
    (net (code "70") (name "unconnected-(IC2-PIO(7)-PadP$22)") (class "Default")
      (node (ref "IC2") (pin "P$22") (pinfunction "PIO(7)_P$22") (pintype "bidirectional"))
    )
    (net (code "71") (name "unconnected-(IC2-PIO(8)-PadP$28)") (class "Default")
      (node (ref "IC2") (pin "P$28") (pinfunction "PIO(8)_P$28") (pintype "bidirectional"))
    )
    (net (code "72") (name "unconnected-(IC2-PIO(9)-PadP$29)") (class "Default")
      (node (ref "IC2") (pin "P$29") (pinfunction "PIO(9)_P$29") (pintype "bidirectional"))
    )
    (net (code "73") (name "unconnected-(IC2-PIO(10)-PadP$30)") (class "Default")
      (node (ref "IC2") (pin "P$30") (pinfunction "PIO(10)_P$30") (pintype "bidirectional"))
    )
    (net (code "74") (name "unconnected-(IC2-PIO(11)-PadP$1)") (class "Default")
      (node (ref "IC2") (pin "P$1") (pinfunction "PIO(11)_P$1") (pintype "bidirectional"))
    )
    (net (code "75") (name "unconnected-(IC2-SPI-CLK-PadP$20)") (class "Default")
      (node (ref "IC2") (pin "P$20") (pinfunction "SPI-CLK_P$20") (pintype "input"))
    )
    (net (code "76") (name "unconnected-(IC2-SPI-CSB-PadP$18)") (class "Default")
      (node (ref "IC2") (pin "P$18") (pinfunction "SPI-CSB_P$18") (pintype "input"))
    )
    (net (code "77") (name "unconnected-(IC2-SPI-MISO-PadP$19)") (class "Default")
      (node (ref "IC2") (pin "P$19") (pinfunction "SPI-MISO_P$19") (pintype "output"))
    )
    (net (code "78") (name "unconnected-(IC2-SPI-MOSI-PadP$17)") (class "Default")
      (node (ref "IC2") (pin "P$17") (pinfunction "SPI-MOSI_P$17") (pintype "input"))
    )
    (net (code "79") (name "unconnected-(IC2-UART-CTS-PadP$8)") (class "Default")
      (node (ref "IC2") (pin "P$8") (pinfunction "UART-CTS_P$8") (pintype "input"))
    )
    (net (code "80") (name "unconnected-(IC2-UART-RTS-PadP$11)") (class "Default")
      (node (ref "IC2") (pin "P$11") (pinfunction "UART-RTS_P$11") (pintype "output"))
    )
    (net (code "81") (name "unconnected-(IC2-USB-DN-PadP$13)") (class "Default")
      (node (ref "IC2") (pin "P$13") (pinfunction "USB-DN_P$13") (pintype "bidirectional"))
    )
    (net (code "82") (name "unconnected-(IC2-USB-DP-PadP$12)") (class "Default")
      (node (ref "IC2") (pin "P$12") (pinfunction "USB-DP_P$12") (pintype "bidirectional"))
    )
    (net (code "83") (name "unconnected-(IC3A-VREF-Pad5)") (class "Default")
      (node (ref "IC3") (pin "5") (pinfunction "VREF_5") (pintype "bidirectional"))
    )
    (net (code "84") (name "unconnected-(U1B-PA8-Pad20)") (class "Default")
      (node (ref "U1") (pin "20") (pinfunction "PA8_20") (pintype "bidirectional"))
    )
    (net (code "85") (name "unconnected-(U1C-PA0-Pad7)") (class "Default")
      (node (ref "U1") (pin "7") (pinfunction "PA0_7") (pintype "bidirectional"))
    )
    (net (code "86") (name "unconnected-(U1C-PA1-Pad8)") (class "Default")
      (node (ref "U1") (pin "8") (pinfunction "PA1_8") (pintype "bidirectional"))
    )
    (net (code "87") (name "unconnected-(U1C-PA5-Pad12)") (class "Default")
      (node (ref "U1") (pin "12") (pinfunction "PA5_12") (pintype "bidirectional"))
    )
  )
)
